# fb_relais_8_230V_86.net
KiCad netlist of a schematic drawn in EAGLE
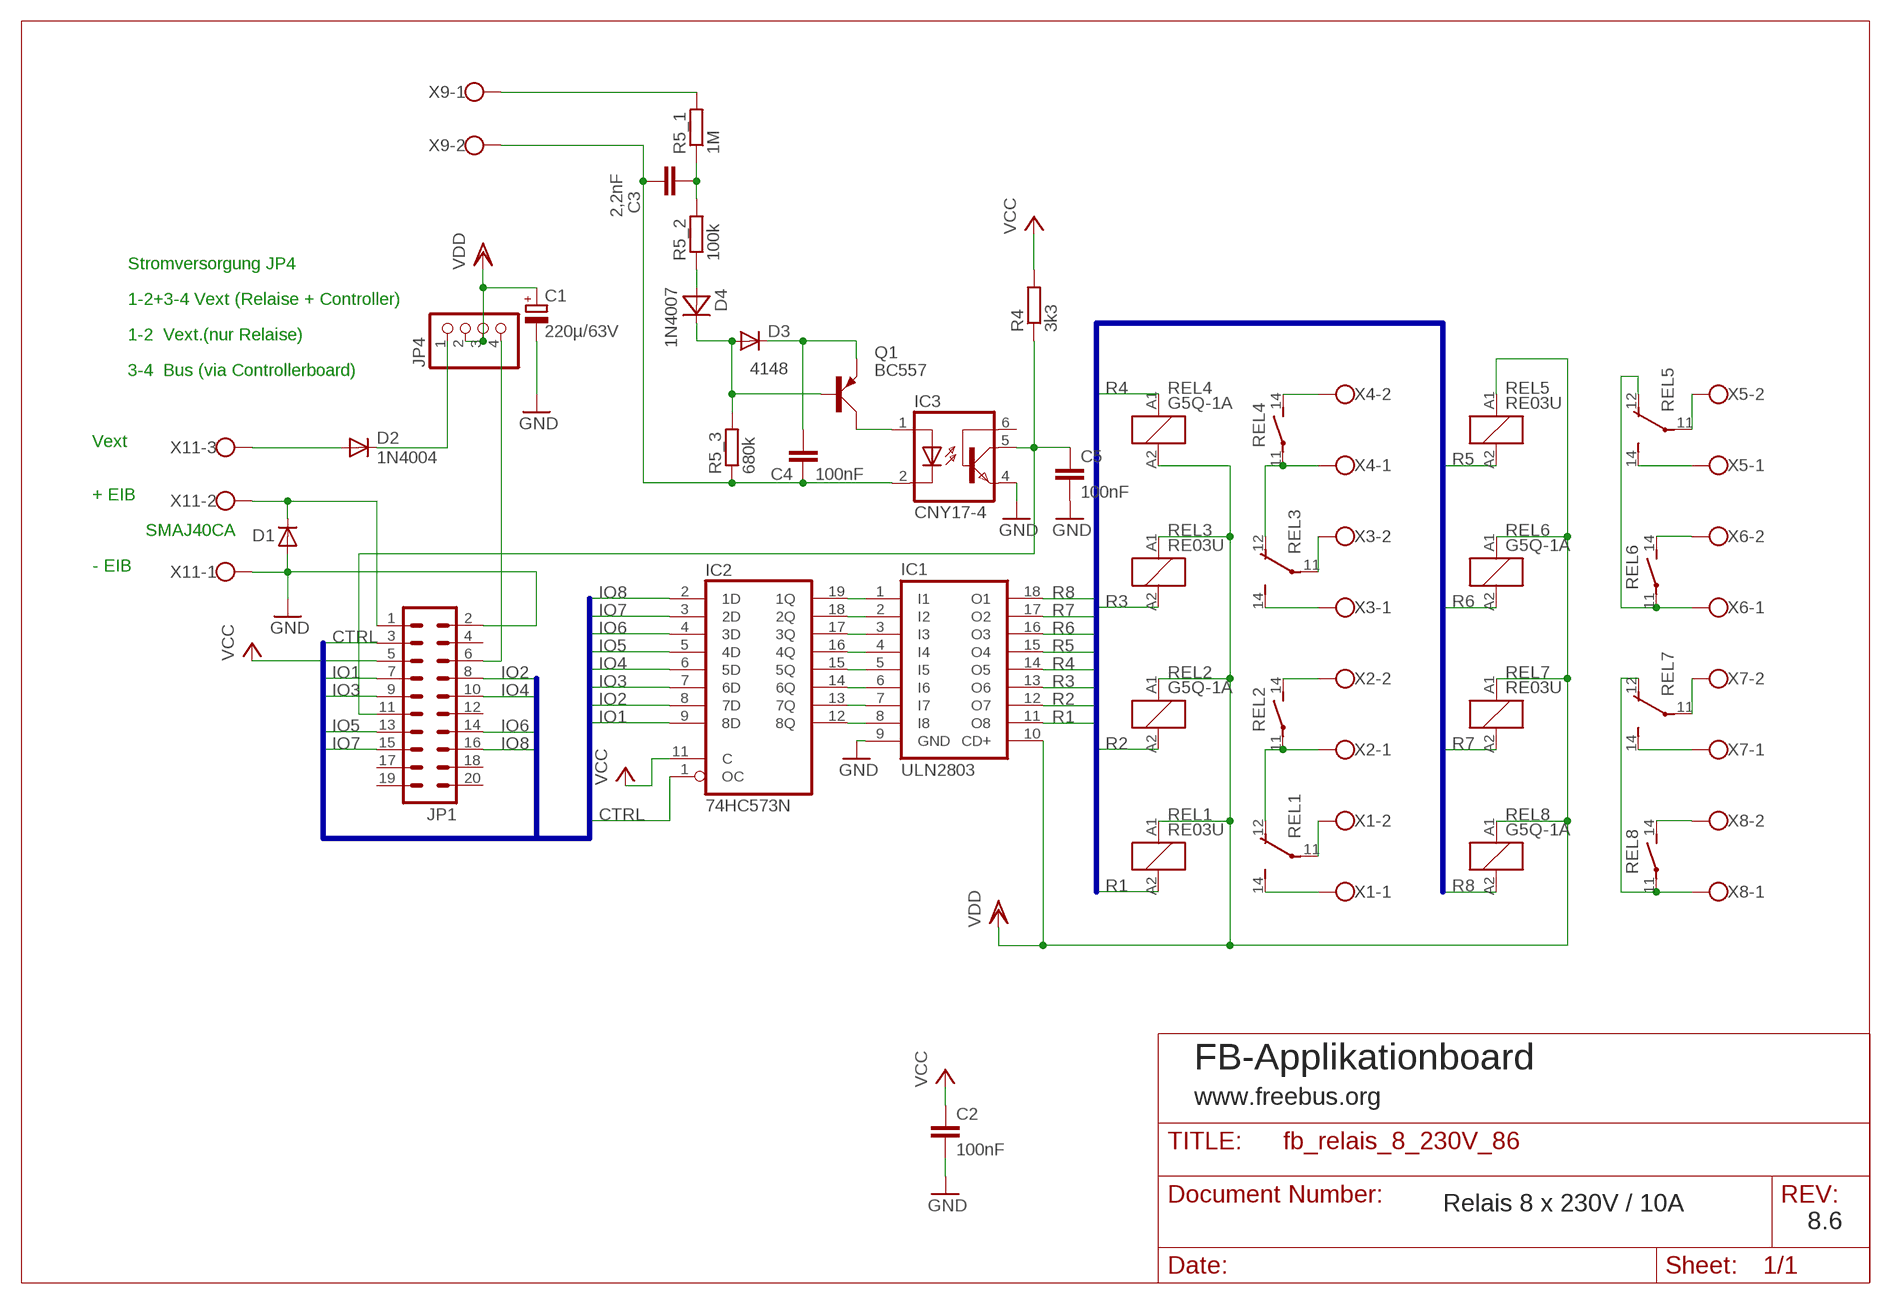
[diagram p0: schematic, sheet 1]

(export (version "E")
  (design (tool "Eeschema 10.0.6"))
  (components
    (comp (ref "C1")
      (value "220µ/63V")
      (footprint "eagle-import:E5-10,5")
      (libsource (lib "eagle-import") (part "CPOL-EUE5-10.5"))
    )
    (comp (ref "C2")
      (value "100nF")
      (footprint "eagle-import:C050-024X044")
      (libsource (lib "eagle-import") (part "C-EU050-024X044"))
    )
    (comp (ref "C3")
      (value "2,2nF")
      (footprint "eagle-import:C102-043X133")
      (libsource (lib "eagle-import") (part "C-EU102-043X133"))
    )
    (comp (ref "C4")
      (value "100nF")
      (footprint "eagle-import:C050-024X044")
      (libsource (lib "eagle-import") (part "C-EU050-024X044"))
    )
    (comp (ref "C5")
      (value "100nF")
      (footprint "eagle-import:C050-024X044")
      (libsource (lib "eagle-import") (part "C-EU050-024X044"))
    )
    (comp (ref "D1")
      (value "D-SMB")
      (footprint "eagle-import:SMB")
      (libsource (lib "eagle-import") (part "D-SMB"))
    )
    (comp (ref "D2")
      (value "1N4004")
      (footprint "eagle-import:DO41-10")
      (libsource (lib "eagle-import") (part "1N4004"))
    )
    (comp (ref "D3")
      (value "4148")
      (footprint "eagle-import:D-2.5")
      (libsource (lib "eagle-import") (part "1N41481448V"))
    )
    (comp (ref "D4")
      (value "1N4007")
      (footprint "eagle-import:DO41-7")
      (libsource (lib "eagle-import") (part "1N4007"))
    )
    (comp (ref "IC1")
      (value "ULN2803")
      (footprint "eagle-import:DIL18")
      (libsource (lib "eagle-import") (part "ULN2803A"))
    )
    (comp (ref "IC2")
      (value "74HC573N")
      (footprint "eagle-import:DIL20")
      (libsource (lib "eagle-import") (part "74573NHC"))
    )
    (comp (ref "IC3")
      (value "CNY17-4")
      (footprint "eagle-import:DIL06")
      (libsource (lib "eagle-import") (part "CNY17"))
    )
    (comp (ref "JP1")
      (value "ML20")
      (footprint "eagle-import:ML20")
      (libsource (lib "eagle-import") (part "ML20"))
    )
    (comp (ref "JP4")
      (value "PINHD-1X4")
      (footprint "eagle-import:1X04")
      (libsource (lib "eagle-import") (part "PINHD-1X4"))
    )
    (comp (ref "Q1")
      (value "BC557")
      (footprint "eagle-import:SOT54A")
      (libsource (lib "eagle-import") (part "BC557"))
    )
    (comp (ref "R4")
      (value "3k3")
      (footprint "eagle-import:0207_7")
      (libsource (lib "eagle-import") (part "R-EU_0207/7"))
    )
    (comp (ref "R5_1")
      (value "1M")
      (footprint "eagle-import:0207_7")
      (libsource (lib "eagle-import") (part "R-EU_0207/7"))
    )
    (comp (ref "R5_2")
      (value "100k")
      (footprint "eagle-import:0207_7")
      (libsource (lib "eagle-import") (part "R-EU_0207/7"))
    )
    (comp (ref "R5_3")
      (value "680k")
      (footprint "eagle-import:0207_7")
      (libsource (lib "eagle-import") (part "R-EU_0207/7"))
    )
    (comp (ref "REL1")
      (value "RE03U")
      (footprint "eagle-import:G5Q_1_EU")
      (libsource (lib "eagle-import") (part "RE03U"))
    )
    (comp (ref "REL2")
      (value "G5Q-1A")
      (footprint "eagle-import:RE-SCHRACK")
      (libsource (lib "eagle-import") (part "RE030024"))
    )
    (comp (ref "REL3")
      (value "RE03U")
      (footprint "eagle-import:G5Q_1_EU")
      (libsource (lib "eagle-import") (part "RE03U"))
    )
    (comp (ref "REL4")
      (value "G5Q-1A")
      (footprint "eagle-import:RE-SCHRACK")
      (libsource (lib "eagle-import") (part "RE030024"))
    )
    (comp (ref "REL5")
      (value "RE03U")
      (footprint "eagle-import:G5Q_1_EU")
      (libsource (lib "eagle-import") (part "RE03U"))
    )
    (comp (ref "REL6")
      (value "G5Q-1A")
      (footprint "eagle-import:RE-SCHRACK")
      (libsource (lib "eagle-import") (part "RE030024"))
    )
    (comp (ref "REL7")
      (value "RE03U")
      (footprint "eagle-import:G5Q_1_EU")
      (libsource (lib "eagle-import") (part "RE03U"))
    )
    (comp (ref "REL8")
      (value "G5Q-1A")
      (footprint "eagle-import:RE-SCHRACK")
      (libsource (lib "eagle-import") (part "RE030024"))
    )
    (comp (ref "X1")
      (value "W237-102")
      (footprint "eagle-import:W237-102")
      (libsource (lib "eagle-import") (part "W237-102"))
    )
    (comp (ref "X2")
      (value "W237-102")
      (footprint "eagle-import:W237-102")
      (libsource (lib "eagle-import") (part "W237-102"))
    )
    (comp (ref "X3")
      (value "W237-102")
      (footprint "eagle-import:W237-102")
      (libsource (lib "eagle-import") (part "W237-102"))
    )
    (comp (ref "X4")
      (value "W237-102")
      (footprint "eagle-import:W237-102")
      (libsource (lib "eagle-import") (part "W237-102"))
    )
    (comp (ref "X5")
      (value "W237-102")
      (footprint "eagle-import:W237-102")
      (libsource (lib "eagle-import") (part "W237-102"))
    )
    (comp (ref "X6")
      (value "W237-102")
      (footprint "eagle-import:W237-102")
      (libsource (lib "eagle-import") (part "W237-102"))
    )
    (comp (ref "X7")
      (value "W237-102")
      (footprint "eagle-import:W237-102")
      (libsource (lib "eagle-import") (part "W237-102"))
    )
    (comp (ref "X8")
      (value "W237-102")
      (footprint "eagle-import:W237-102")
      (libsource (lib "eagle-import") (part "W237-102"))
    )
    (comp (ref "X9")
      (value "W237-102")
      (footprint "eagle-import:W237-102")
      (libsource (lib "eagle-import") (part "W237-102"))
    )
    (comp (ref "X11")
      (value "W237-3E")
      (footprint "eagle-import:W237-3E")
      (libsource (lib "eagle-import") (part "W237-3E"))
    )
  )
  (nets
    (net (code "1") (name "/CTRL") (class "Default")
      (node (ref "IC2") (pin "1") (pinfunction "OC_1") (pintype "input"))
      (node (ref "JP1") (pin "3") (pinfunction "3_3") (pintype "passive"))
    )
    (net (code "2") (name "/IO1") (class "Default")
      (node (ref "IC2") (pin "9") (pinfunction "8D_9") (pintype "input"))
      (node (ref "JP1") (pin "7") (pinfunction "7_7") (pintype "passive"))
    )
    (net (code "3") (name "/IO2") (class "Default")
      (node (ref "IC2") (pin "8") (pinfunction "7D_8") (pintype "input"))
      (node (ref "JP1") (pin "8") (pinfunction "8_8") (pintype "passive"))
    )
    (net (code "4") (name "/IO3") (class "Default")
      (node (ref "IC2") (pin "7") (pinfunction "6D_7") (pintype "input"))
      (node (ref "JP1") (pin "9") (pinfunction "9_9") (pintype "passive"))
    )
    (net (code "5") (name "/IO4") (class "Default")
      (node (ref "IC2") (pin "6") (pinfunction "5D_6") (pintype "input"))
      (node (ref "JP1") (pin "10") (pinfunction "10_10") (pintype "passive"))
    )
    (net (code "6") (name "/IO5") (class "Default")
      (node (ref "IC2") (pin "5") (pinfunction "4D_5") (pintype "input"))
      (node (ref "JP1") (pin "13") (pinfunction "13_13") (pintype "passive"))
    )
    (net (code "7") (name "/IO6") (class "Default")
      (node (ref "IC2") (pin "4") (pinfunction "3D_4") (pintype "input"))
      (node (ref "JP1") (pin "14") (pinfunction "14_14") (pintype "passive"))
    )
    (net (code "8") (name "/IO7") (class "Default")
      (node (ref "IC2") (pin "3") (pinfunction "2D_3") (pintype "input"))
      (node (ref "JP1") (pin "15") (pinfunction "15_15") (pintype "passive"))
    )
    (net (code "9") (name "/IO8") (class "Default")
      (node (ref "IC2") (pin "2") (pinfunction "1D_2") (pintype "input"))
      (node (ref "JP1") (pin "16") (pinfunction "16_16") (pintype "passive"))
    )
    (net (code "10") (name "/R1") (class "Default")
      (node (ref "IC1") (pin "11") (pinfunction "O8_11") (pintype "open_collector"))
      (node (ref "REL1") (pin "A2") (pinfunction "2_A2") (pintype "passive"))
    )
    (net (code "11") (name "/R2") (class "Default")
      (node (ref "IC1") (pin "12") (pinfunction "O7_12") (pintype "open_collector"))
      (node (ref "REL2") (pin "A2") (pinfunction "2_A2") (pintype "passive"))
    )
    (net (code "12") (name "/R3") (class "Default")
      (node (ref "IC1") (pin "13") (pinfunction "O6_13") (pintype "open_collector"))
      (node (ref "REL3") (pin "A2") (pinfunction "2_A2") (pintype "passive"))
    )
    (net (code "13") (name "/R4") (class "Default")
      (node (ref "IC1") (pin "14") (pinfunction "O5_14") (pintype "open_collector"))
      (node (ref "REL4") (pin "A1") (pinfunction "1_A1") (pintype "passive"))
    )
    (net (code "14") (name "/R5") (class "Default")
      (node (ref "IC1") (pin "15") (pinfunction "O4_15") (pintype "open_collector"))
      (node (ref "REL5") (pin "A2") (pinfunction "2_A2") (pintype "passive"))
    )
    (net (code "15") (name "/R6") (class "Default")
      (node (ref "IC1") (pin "16") (pinfunction "O3_16") (pintype "open_collector"))
      (node (ref "REL6") (pin "A2") (pinfunction "2_A2") (pintype "passive"))
    )
    (net (code "16") (name "/R7") (class "Default")
      (node (ref "IC1") (pin "17") (pinfunction "O2_17") (pintype "open_collector"))
      (node (ref "REL7") (pin "A2") (pinfunction "2_A2") (pintype "passive"))
    )
    (net (code "17") (name "/R8") (class "Default")
      (node (ref "IC1") (pin "18") (pinfunction "O1_18") (pintype "open_collector"))
      (node (ref "REL8") (pin "A2") (pinfunction "2_A2") (pintype "passive"))
    )
    (net (code "18") (name "GND") (class "Default")
      (node (ref "C1") (pin "-") (pinfunction "-_-") (pintype "passive"))
      (node (ref "C2") (pin "2") (pinfunction "2_2") (pintype "passive"))
      (node (ref "C5") (pin "2") (pinfunction "2_2") (pintype "passive"))
      (node (ref "D1") (pin "2") (pinfunction "A_2") (pintype "passive"))
      (node (ref "IC1") (pin "9") (pinfunction "GND_9") (pintype "power_in"))
      (node (ref "IC3") (pin "4") (pinfunction "EMI_4") (pintype "passive"))
      (node (ref "JP1") (pin "2") (pinfunction "2_2") (pintype "passive"))
      (node (ref "X11") (pin "1") (pinfunction "KL_1") (pintype "passive"))
    )
    (net (code "19") (name "Net-(C3-Pad1)") (class "Default")
      (node (ref "C3") (pin "1") (pinfunction "1_1") (pintype "passive"))
      (node (ref "R5_1") (pin "1") (pinfunction "1_1") (pintype "passive"))
      (node (ref "R5_2") (pin "2") (pinfunction "2_2") (pintype "passive"))
    )
    (net (code "20") (name "Net-(C4-Pad2)") (class "Default")
      (node (ref "C4") (pin "2") (pinfunction "2_2") (pintype "passive"))
      (node (ref "D3") (pin "C") (pinfunction "C_C") (pintype "passive"))
      (node (ref "Q1") (pin "E") (pinfunction "E_E") (pintype "passive"))
    )
    (net (code "21") (name "Net-(D1-C)") (class "Default")
      (node (ref "D1") (pin "1") (pinfunction "C_1") (pintype "passive"))
      (node (ref "JP1") (pin "1") (pinfunction "1_1") (pintype "passive"))
      (node (ref "X11") (pin "2") (pinfunction "KL_2") (pintype "passive"))
    )
    (net (code "22") (name "Net-(D2-PadC)") (class "Default")
      (node (ref "D2") (pin "C") (pinfunction "C_C") (pintype "passive"))
      (node (ref "JP4") (pin "1") (pinfunction "1_1") (pintype "passive"))
    )
    (net (code "23") (name "Net-(D3-PadA)") (class "Default")
      (node (ref "D3") (pin "A") (pinfunction "A_A") (pintype "passive"))
      (node (ref "D4") (pin "C") (pinfunction "C_C") (pintype "passive"))
      (node (ref "Q1") (pin "B") (pinfunction "B_B") (pintype "passive"))
      (node (ref "R5_3") (pin "2") (pinfunction "2_2") (pintype "passive"))
    )
    (net (code "24") (name "Net-(D4-PadA)") (class "Default")
      (node (ref "D4") (pin "A") (pinfunction "A_A") (pintype "passive"))
      (node (ref "R5_2") (pin "1") (pinfunction "1_1") (pintype "passive"))
    )
    (net (code "25") (name "Net-(IC1-I1)") (class "Default")
      (node (ref "IC1") (pin "1") (pinfunction "I1_1") (pintype "input"))
      (node (ref "IC2") (pin "19") (pinfunction "1Q_19") (pintype "tri_state"))
    )
    (net (code "26") (name "Net-(IC1-I2)") (class "Default")
      (node (ref "IC1") (pin "2") (pinfunction "I2_2") (pintype "input"))
      (node (ref "IC2") (pin "18") (pinfunction "2Q_18") (pintype "tri_state"))
    )
    (net (code "27") (name "Net-(IC1-I3)") (class "Default")
      (node (ref "IC1") (pin "3") (pinfunction "I3_3") (pintype "input"))
      (node (ref "IC2") (pin "17") (pinfunction "3Q_17") (pintype "tri_state"))
    )
    (net (code "28") (name "Net-(IC1-I4)") (class "Default")
      (node (ref "IC1") (pin "4") (pinfunction "I4_4") (pintype "input"))
      (node (ref "IC2") (pin "16") (pinfunction "4Q_16") (pintype "tri_state"))
    )
    (net (code "29") (name "Net-(IC1-I5)") (class "Default")
      (node (ref "IC1") (pin "5") (pinfunction "I5_5") (pintype "input"))
      (node (ref "IC2") (pin "15") (pinfunction "5Q_15") (pintype "tri_state"))
    )
    (net (code "30") (name "Net-(IC1-I6)") (class "Default")
      (node (ref "IC1") (pin "6") (pinfunction "I6_6") (pintype "input"))
      (node (ref "IC2") (pin "14") (pinfunction "6Q_14") (pintype "tri_state"))
    )
    (net (code "31") (name "Net-(IC1-I7)") (class "Default")
      (node (ref "IC1") (pin "7") (pinfunction "I7_7") (pintype "input"))
      (node (ref "IC2") (pin "13") (pinfunction "7Q_13") (pintype "tri_state"))
    )
    (net (code "32") (name "Net-(IC1-I8)") (class "Default")
      (node (ref "IC1") (pin "8") (pinfunction "I8_8") (pintype "input"))
      (node (ref "IC2") (pin "12") (pinfunction "8Q_12") (pintype "tri_state"))
    )
    (net (code "33") (name "Net-(IC3-A)") (class "Default")
      (node (ref "IC3") (pin "1") (pinfunction "A_1") (pintype "passive"))
      (node (ref "Q1") (pin "C") (pinfunction "C_C") (pintype "passive"))
    )
    (net (code "34") (name "Net-(IC3-C)") (class "Default")
      (node (ref "C3") (pin "2") (pinfunction "2_2") (pintype "passive"))
      (node (ref "C4") (pin "1") (pinfunction "1_1") (pintype "passive"))
      (node (ref "IC3") (pin "2") (pinfunction "C_2") (pintype "passive"))
      (node (ref "R5_3") (pin "1") (pinfunction "1_1") (pintype "passive"))
      (node (ref "X9") (pin "2") (pinfunction "KL_2") (pintype "passive"))
    )
    (net (code "35") (name "Net-(IC3-COL)") (class "Default")
      (node (ref "C5") (pin "1") (pinfunction "1_1") (pintype "passive"))
      (node (ref "IC3") (pin "5") (pinfunction "COL_5") (pintype "passive"))
      (node (ref "JP1") (pin "11") (pinfunction "11_11") (pintype "passive"))
      (node (ref "R4") (pin "1") (pinfunction "1_1") (pintype "passive"))
    )
    (net (code "36") (name "Net-(JP1-Pad6)") (class "Default")
      (node (ref "JP1") (pin "6") (pinfunction "6_6") (pintype "passive"))
      (node (ref "JP4") (pin "4") (pinfunction "4_4") (pintype "passive"))
    )
    (net (code "37") (name "Net-(REL1A-O)") (class "Default")
      (node (ref "REL1") (pin "12") (pinfunction "O_12") (pintype "passive"))
      (node (ref "REL2") (pin "11") (pinfunction "P_11") (pintype "passive"))
      (node (ref "X2") (pin "1") (pinfunction "KL_1") (pintype "passive"))
    )
    (net (code "38") (name "Net-(REL1A-P)") (class "Default")
      (node (ref "REL1") (pin "11") (pinfunction "P_11") (pintype "passive"))
      (node (ref "X1") (pin "2") (pinfunction "KL_2") (pintype "passive"))
    )
    (net (code "39") (name "Net-(REL1A-S)") (class "Default")
      (node (ref "REL1") (pin "14") (pinfunction "S_14") (pintype "passive"))
      (node (ref "X1") (pin "1") (pinfunction "KL_1") (pintype "passive"))
    )
    (net (code "40") (name "Net-(REL2B-S)") (class "Default")
      (node (ref "REL2") (pin "14") (pinfunction "S_14") (pintype "passive"))
      (node (ref "X2") (pin "2") (pinfunction "KL_2") (pintype "passive"))
    )
    (net (code "41") (name "Net-(REL3A-O)") (class "Default")
      (node (ref "REL3") (pin "12") (pinfunction "O_12") (pintype "passive"))
      (node (ref "REL4") (pin "11") (pinfunction "P_11") (pintype "passive"))
      (node (ref "X4") (pin "1") (pinfunction "KL_1") (pintype "passive"))
    )
    (net (code "42") (name "Net-(REL3A-P)") (class "Default")
      (node (ref "REL3") (pin "11") (pinfunction "P_11") (pintype "passive"))
      (node (ref "X3") (pin "2") (pinfunction "KL_2") (pintype "passive"))
    )
    (net (code "43") (name "Net-(REL3A-S)") (class "Default")
      (node (ref "REL3") (pin "14") (pinfunction "S_14") (pintype "passive"))
      (node (ref "X3") (pin "1") (pinfunction "KL_1") (pintype "passive"))
    )
    (net (code "44") (name "Net-(REL4B-S)") (class "Default")
      (node (ref "REL4") (pin "14") (pinfunction "S_14") (pintype "passive"))
      (node (ref "X4") (pin "2") (pinfunction "KL_2") (pintype "passive"))
    )
    (net (code "45") (name "Net-(REL5A-O)") (class "Default")
      (node (ref "REL5") (pin "12") (pinfunction "O_12") (pintype "passive"))
      (node (ref "REL6") (pin "11") (pinfunction "P_11") (pintype "passive"))
      (node (ref "X6") (pin "1") (pinfunction "KL_1") (pintype "passive"))
    )
    (net (code "46") (name "Net-(REL5A-P)") (class "Default")
      (node (ref "REL5") (pin "11") (pinfunction "P_11") (pintype "passive"))
      (node (ref "X5") (pin "2") (pinfunction "KL_2") (pintype "passive"))
    )
    (net (code "47") (name "Net-(REL5A-S)") (class "Default")
      (node (ref "REL5") (pin "14") (pinfunction "S_14") (pintype "passive"))
      (node (ref "X5") (pin "1") (pinfunction "KL_1") (pintype "passive"))
    )
    (net (code "48") (name "Net-(REL6B-S)") (class "Default")
      (node (ref "REL6") (pin "14") (pinfunction "S_14") (pintype "passive"))
      (node (ref "X6") (pin "2") (pinfunction "KL_2") (pintype "passive"))
    )
    (net (code "49") (name "Net-(REL7A-O)") (class "Default")
      (node (ref "REL7") (pin "12") (pinfunction "O_12") (pintype "passive"))
      (node (ref "REL8") (pin "11") (pinfunction "P_11") (pintype "passive"))
      (node (ref "X8") (pin "1") (pinfunction "KL_1") (pintype "passive"))
    )
    (net (code "50") (name "Net-(REL7A-P)") (class "Default")
      (node (ref "REL7") (pin "11") (pinfunction "P_11") (pintype "passive"))
      (node (ref "X7") (pin "2") (pinfunction "KL_2") (pintype "passive"))
    )
    (net (code "51") (name "Net-(REL7A-S)") (class "Default")
      (node (ref "REL7") (pin "14") (pinfunction "S_14") (pintype "passive"))
      (node (ref "X7") (pin "1") (pinfunction "KL_1") (pintype "passive"))
    )
    (net (code "52") (name "Net-(REL8B-S)") (class "Default")
      (node (ref "REL8") (pin "14") (pinfunction "S_14") (pintype "passive"))
      (node (ref "X8") (pin "2") (pinfunction "KL_2") (pintype "passive"))
    )
    (net (code "53") (name "Net-(X9A-KL)") (class "Default")
      (node (ref "R5_1") (pin "2") (pinfunction "2_2") (pintype "passive"))
      (node (ref "X9") (pin "1") (pinfunction "KL_1") (pintype "passive"))
    )
    (net (code "54") (name "Net-(X11C-KL)") (class "Default")
      (node (ref "D2") (pin "A") (pinfunction "A_A") (pintype "passive"))
      (node (ref "X11") (pin "3") (pinfunction "KL_3") (pintype "passive"))
    )
    (net (code "55") (name "VCC") (class "Default")
      (node (ref "C2") (pin "1") (pinfunction "1_1") (pintype "passive"))
      (node (ref "IC2") (pin "11") (pinfunction "C_11") (pintype "input"))
      (node (ref "JP1") (pin "5") (pinfunction "5_5") (pintype "passive"))
      (node (ref "R4") (pin "2") (pinfunction "2_2") (pintype "passive"))
    )
    (net (code "56") (name "VDD") (class "Default")
      (node (ref "C1") (pin "+") (pinfunction "+_+") (pintype "passive"))
      (node (ref "IC1") (pin "10") (pinfunction "CD+_10") (pintype "passive"))
      (node (ref "JP4") (pin "2") (pinfunction "2_2") (pintype "passive"))
      (node (ref "JP4") (pin "3") (pinfunction "3_3") (pintype "passive"))
      (node (ref "REL1") (pin "A1") (pinfunction "1_A1") (pintype "passive"))
      (node (ref "REL2") (pin "A1") (pinfunction "1_A1") (pintype "passive"))
      (node (ref "REL3") (pin "A1") (pinfunction "1_A1") (pintype "passive"))
      (node (ref "REL4") (pin "A2") (pinfunction "2_A2") (pintype "passive"))
      (node (ref "REL5") (pin "A1") (pinfunction "1_A1") (pintype "passive"))
      (node (ref "REL6") (pin "A1") (pinfunction "1_A1") (pintype "passive"))
      (node (ref "REL7") (pin "A1") (pinfunction "1_A1") (pintype "passive"))
      (node (ref "REL8") (pin "A1") (pinfunction "1_A1") (pintype "passive"))
    )
    (net (code "57") (name "unconnected-(IC3-BAS-Pad6)") (class "Default")
      (node (ref "IC3") (pin "6") (pinfunction "BAS_6") (pintype "passive"))
    )
    (net (code "58") (name "unconnected-(JP1-Pad4)") (class "Default")
      (node (ref "JP1") (pin "4") (pinfunction "4_4") (pintype "passive"))
    )
    (net (code "59") (name "unconnected-(JP1-Pad12)") (class "Default")
      (node (ref "JP1") (pin "12") (pinfunction "12_12") (pintype "passive"))
    )
    (net (code "60") (name "unconnected-(JP1-Pad17)") (class "Default")
      (node (ref "JP1") (pin "17") (pinfunction "17_17") (pintype "passive"))
    )
    (net (code "61") (name "unconnected-(JP1-Pad18)") (class "Default")
      (node (ref "JP1") (pin "18") (pinfunction "18_18") (pintype "passive"))
    )
    (net (code "62") (name "unconnected-(JP1-Pad19)") (class "Default")
      (node (ref "JP1") (pin "19") (pinfunction "19_19") (pintype "passive"))
    )
    (net (code "63") (name "unconnected-(JP1-Pad20)") (class "Default")
      (node (ref "JP1") (pin "20") (pinfunction "20_20") (pintype "passive"))
    )
  )
)
